# Microcontroller.net
KiCad netlist of a schematic drawn in Altium Designer
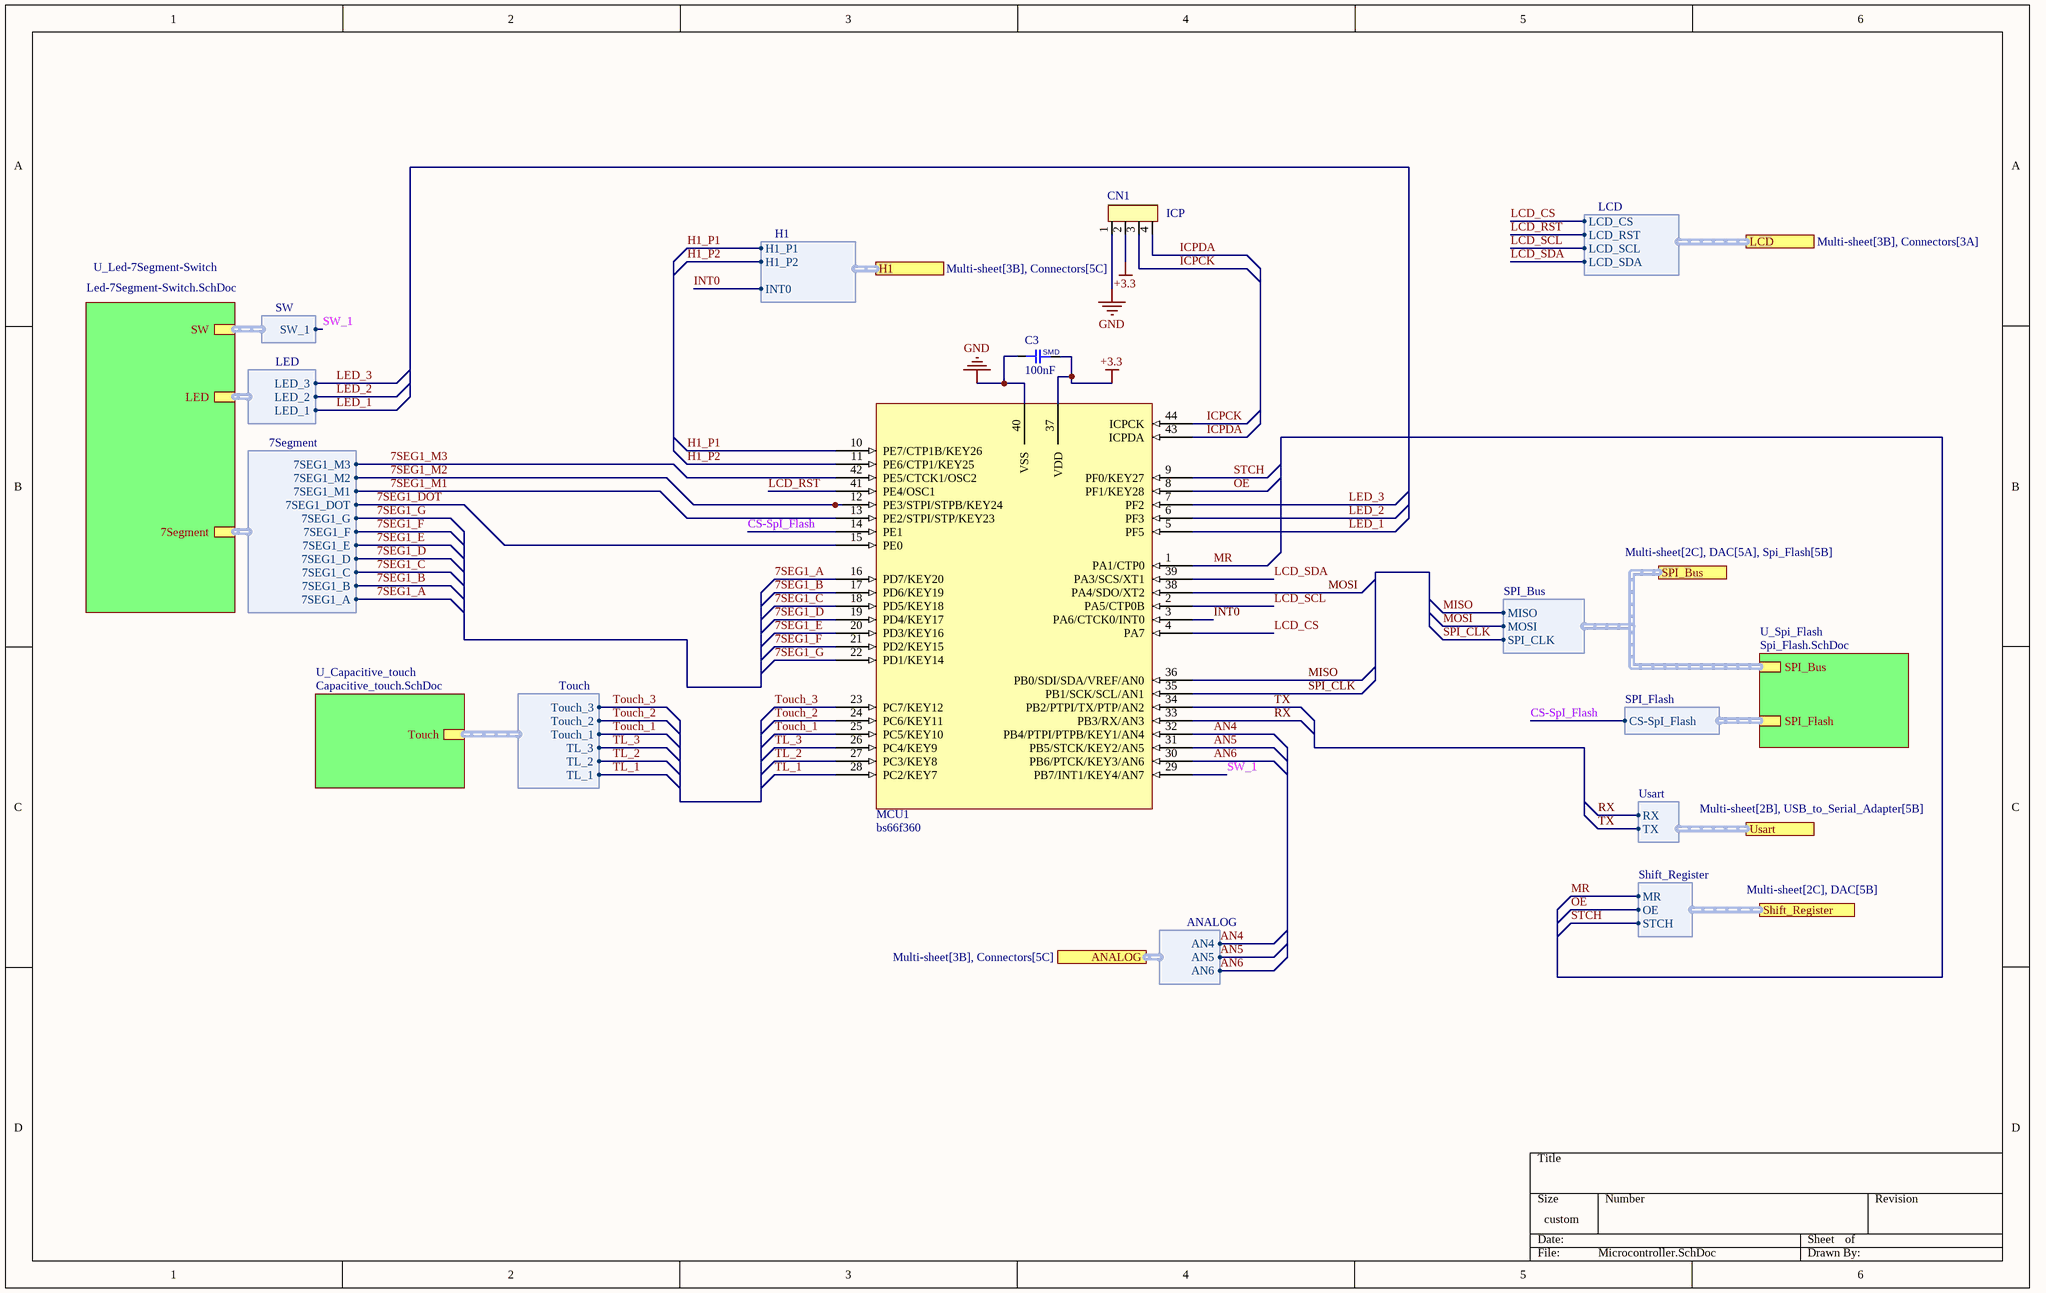
[diagram p0: Microcontroller.SchDoc]

(export (version "E")
  (design (tool "Eeschema 10.0.6"))
  (components
    (comp (ref "C3") (value "100nF") (footprint "CAP-0603") (libsource (lib "kave-eng-pro") (part "cap_smd")))
    (comp (ref "CN1")
      (value "ICP")
      (footprint "CONECTOR/XH/4PIN")
      (libsource (lib "kave-eng-pro") (part "CONECTOR/XH/4PIN"))
    )
    (comp (ref "MCU1")
      (value "bs66f360")
      (footprint "bs66f360")
      (libsource (lib "kave-eng-pro") (part "bs66f360"))
    )
  )
  (nets
    (net (code "12") (name "+3.3") (class "Default")
      (node (ref "C3") (pin "2") (pintype "passive"))
      (node (ref "CN1") (pin "2") (pintype "power_in"))
      (node (ref "MCU1") (pin "37") (pinfunction "VDD_37") (pintype "power_in"))
    )
    (net (code "13") (name "/7SEG1_A") (class "Default")
      (node (ref "MCU1") (pin "16") (pinfunction "PD7/KEY20_16") (pintype "input"))
    )
    (net (code "14") (name "/7SEG1_B") (class "Default")
      (node (ref "MCU1") (pin "17") (pinfunction "PD6/KEY19_17") (pintype "input"))
    )
    (net (code "15") (name "/7SEG1_C") (class "Default")
      (node (ref "MCU1") (pin "18") (pinfunction "PD5/KEY18_18") (pintype "input"))
    )
    (net (code "16") (name "/7SEG1_D") (class "Default")
      (node (ref "MCU1") (pin "19") (pinfunction "PD4/KEY17_19") (pintype "input"))
    )
    (net (code "17") (name "/7SEG1_DOT") (class "Default")
      (node (ref "MCU1") (pin "15") (pinfunction "PE0_15") (pintype "input"))
    )
    (net (code "18") (name "/7SEG1_E") (class "Default")
      (node (ref "MCU1") (pin "20") (pinfunction "PD3/KEY16_20") (pintype "input"))
    )
    (net (code "19") (name "/7SEG1_F") (class "Default")
      (node (ref "MCU1") (pin "21") (pinfunction "PD2/KEY15_21") (pintype "input"))
    )
    (net (code "20") (name "/7SEG1_G") (class "Default")
      (node (ref "MCU1") (pin "22") (pinfunction "PD1/KEY14_22") (pintype "input"))
    )
    (net (code "21") (name "/7SEG1_M1") (class "Default")
      (node (ref "MCU1") (pin "13") (pinfunction "PE2/STPI/STP/KEY23_13") (pintype "input"))
    )
    (net (code "22") (name "/7SEG1_M2") (class "Default")
      (node (ref "MCU1") (pin "12") (pinfunction "PE3/STPI/STPB/KEY24_12") (pintype "input"))
    )
    (net (code "23") (name "/7SEG1_M3") (class "Default")
      (node (ref "MCU1") (pin "42") (pinfunction "PE5/CTCK1/OSC2_42") (pintype "input"))
    )
    (net (code "24") (name "/AN4") (class "Default")
      (node (ref "MCU1") (pin "32") (pinfunction "PB4/PTPI/PTPB/KEY1/AN4_32") (pintype "input"))
    )
    (net (code "25") (name "/AN5") (class "Default")
      (node (ref "MCU1") (pin "31") (pinfunction "PB5/STCK/KEY2/AN5_31") (pintype "input"))
    )
    (net (code "26") (name "/AN6") (class "Default")
      (node (ref "MCU1") (pin "30") (pinfunction "PB6/PTCK/KEY3/AN6_30") (pintype "input"))
    )
    (net (code "27") (name "/CS-SpI_Flash") (class "Default")
      (node (ref "MCU1") (pin "14") (pinfunction "PE1_14") (pintype "input"))
    )
    (net (code "28") (name "/H1_P1") (class "Default")
      (node (ref "MCU1") (pin "10") (pinfunction "PE7/CTP1B/KEY26_10") (pintype "input"))
    )
    (net (code "29") (name "/H1_P2") (class "Default")
      (node (ref "MCU1") (pin "11") (pinfunction "PE6/CTP1/KEY25_11") (pintype "input"))
    )
    (net (code "30") (name "/ICPCK") (class "Default")
      (node (ref "CN1") (pin "3") (pintype "power_in"))
      (node (ref "MCU1") (pin "44") (pinfunction "ICPCK_44") (pintype "input"))
    )
    (net (code "31") (name "/ICPDA") (class "Default")
      (node (ref "CN1") (pin "4") (pintype "power_in"))
      (node (ref "MCU1") (pin "43") (pinfunction "ICPDA_43") (pintype "input"))
    )
    (net (code "32") (name "/INT0") (class "Default")
      (node (ref "MCU1") (pin "3") (pinfunction "PA6/CTCK0/INT0_3") (pintype "input"))
    )
    (net (code "33") (name "/LCD_CS") (class "Default")
      (node (ref "MCU1") (pin "4") (pinfunction "PA7_4") (pintype "input"))
    )
    (net (code "34") (name "/LCD_RST") (class "Default")
      (node (ref "MCU1") (pin "41") (pinfunction "PE4/OSC1_41") (pintype "input"))
    )
    (net (code "35") (name "/LCD_SCL") (class "Default")
      (node (ref "MCU1") (pin "2") (pinfunction "PA5/CTP0B_2") (pintype "input"))
    )
    (net (code "36") (name "/LCD_SDA") (class "Default")
      (node (ref "MCU1") (pin "39") (pinfunction "PA3/SCS/XT1_39") (pintype "input"))
    )
    (net (code "37") (name "/LED_1") (class "Default")
      (node (ref "MCU1") (pin "5") (pinfunction "PF5_5") (pintype "input"))
    )
    (net (code "38") (name "/LED_2") (class "Default")
      (node (ref "MCU1") (pin "6") (pinfunction "PF3_6") (pintype "input"))
    )
    (net (code "39") (name "/LED_3") (class "Default")
      (node (ref "MCU1") (pin "7") (pinfunction "PF2_7") (pintype "input"))
    )
    (net (code "40") (name "/MISO") (class "Default")
      (node (ref "MCU1") (pin "36") (pinfunction "PB0/SDI/SDA/VREF/AN0_36") (pintype "input"))
    )
    (net (code "41") (name "/MOSI") (class "Default")
      (node (ref "MCU1") (pin "38") (pinfunction "PA4/SDO/XT2_38") (pintype "input"))
    )
    (net (code "42") (name "/MR") (class "Default")
      (node (ref "MCU1") (pin "1") (pinfunction "PA1/CTP0_1") (pintype "input"))
    )
    (net (code "43") (name "/OE") (class "Default")
      (node (ref "MCU1") (pin "8") (pinfunction "PF1/KEY28_8") (pintype "input"))
    )
    (net (code "44") (name "/RX") (class "Default")
      (node (ref "MCU1") (pin "33") (pinfunction "PB3/RX/AN3_33") (pintype "input"))
    )
    (net (code "45") (name "/SPI_CLK") (class "Default")
      (node (ref "MCU1") (pin "35") (pinfunction "PB1/SCK/SCL/AN1_35") (pintype "input"))
    )
    (net (code "46") (name "/STCH") (class "Default")
      (node (ref "MCU1") (pin "9") (pinfunction "PF0/KEY27_9") (pintype "input"))
    )
    (net (code "47") (name "/SW_1") (class "Default")
      (node (ref "MCU1") (pin "29") (pinfunction "PB7/INT1/KEY4/AN7_29") (pintype "input"))
    )
    (net (code "48") (name "/TL_1") (class "Default")
      (node (ref "MCU1") (pin "28") (pinfunction "PC2/KEY7_28") (pintype "input"))
    )
    (net (code "49") (name "/TL_2") (class "Default")
      (node (ref "MCU1") (pin "27") (pinfunction "PC3/KEY8_27") (pintype "input"))
    )
    (net (code "50") (name "/TL_3") (class "Default")
      (node (ref "MCU1") (pin "26") (pinfunction "PC4/KEY9_26") (pintype "input"))
    )
    (net (code "51") (name "/TX") (class "Default")
      (node (ref "MCU1") (pin "34") (pinfunction "PB2/PTPI/TX/PTP/AN2_34") (pintype "input"))
    )
    (net (code "52") (name "/Touch_1") (class "Default")
      (node (ref "MCU1") (pin "25") (pinfunction "PC5/KEY10_25") (pintype "input"))
    )
    (net (code "53") (name "/Touch_2") (class "Default")
      (node (ref "MCU1") (pin "24") (pinfunction "PC6/KEY11_24") (pintype "input"))
    )
    (net (code "54") (name "/Touch_3") (class "Default")
      (node (ref "MCU1") (pin "23") (pinfunction "PC7/KEY12_23") (pintype "input"))
    )
    (net (code "66") (name "GND") (class "Default")
      (node (ref "C3") (pin "1") (pintype "passive"))
      (node (ref "CN1") (pin "1") (pintype "power_in"))
      (node (ref "MCU1") (pin "40") (pinfunction "VSS_40") (pintype "power_in"))
    )
  )
)
